# Sheet1.net
KiCad netlist of a schematic drawn in Altium Designer
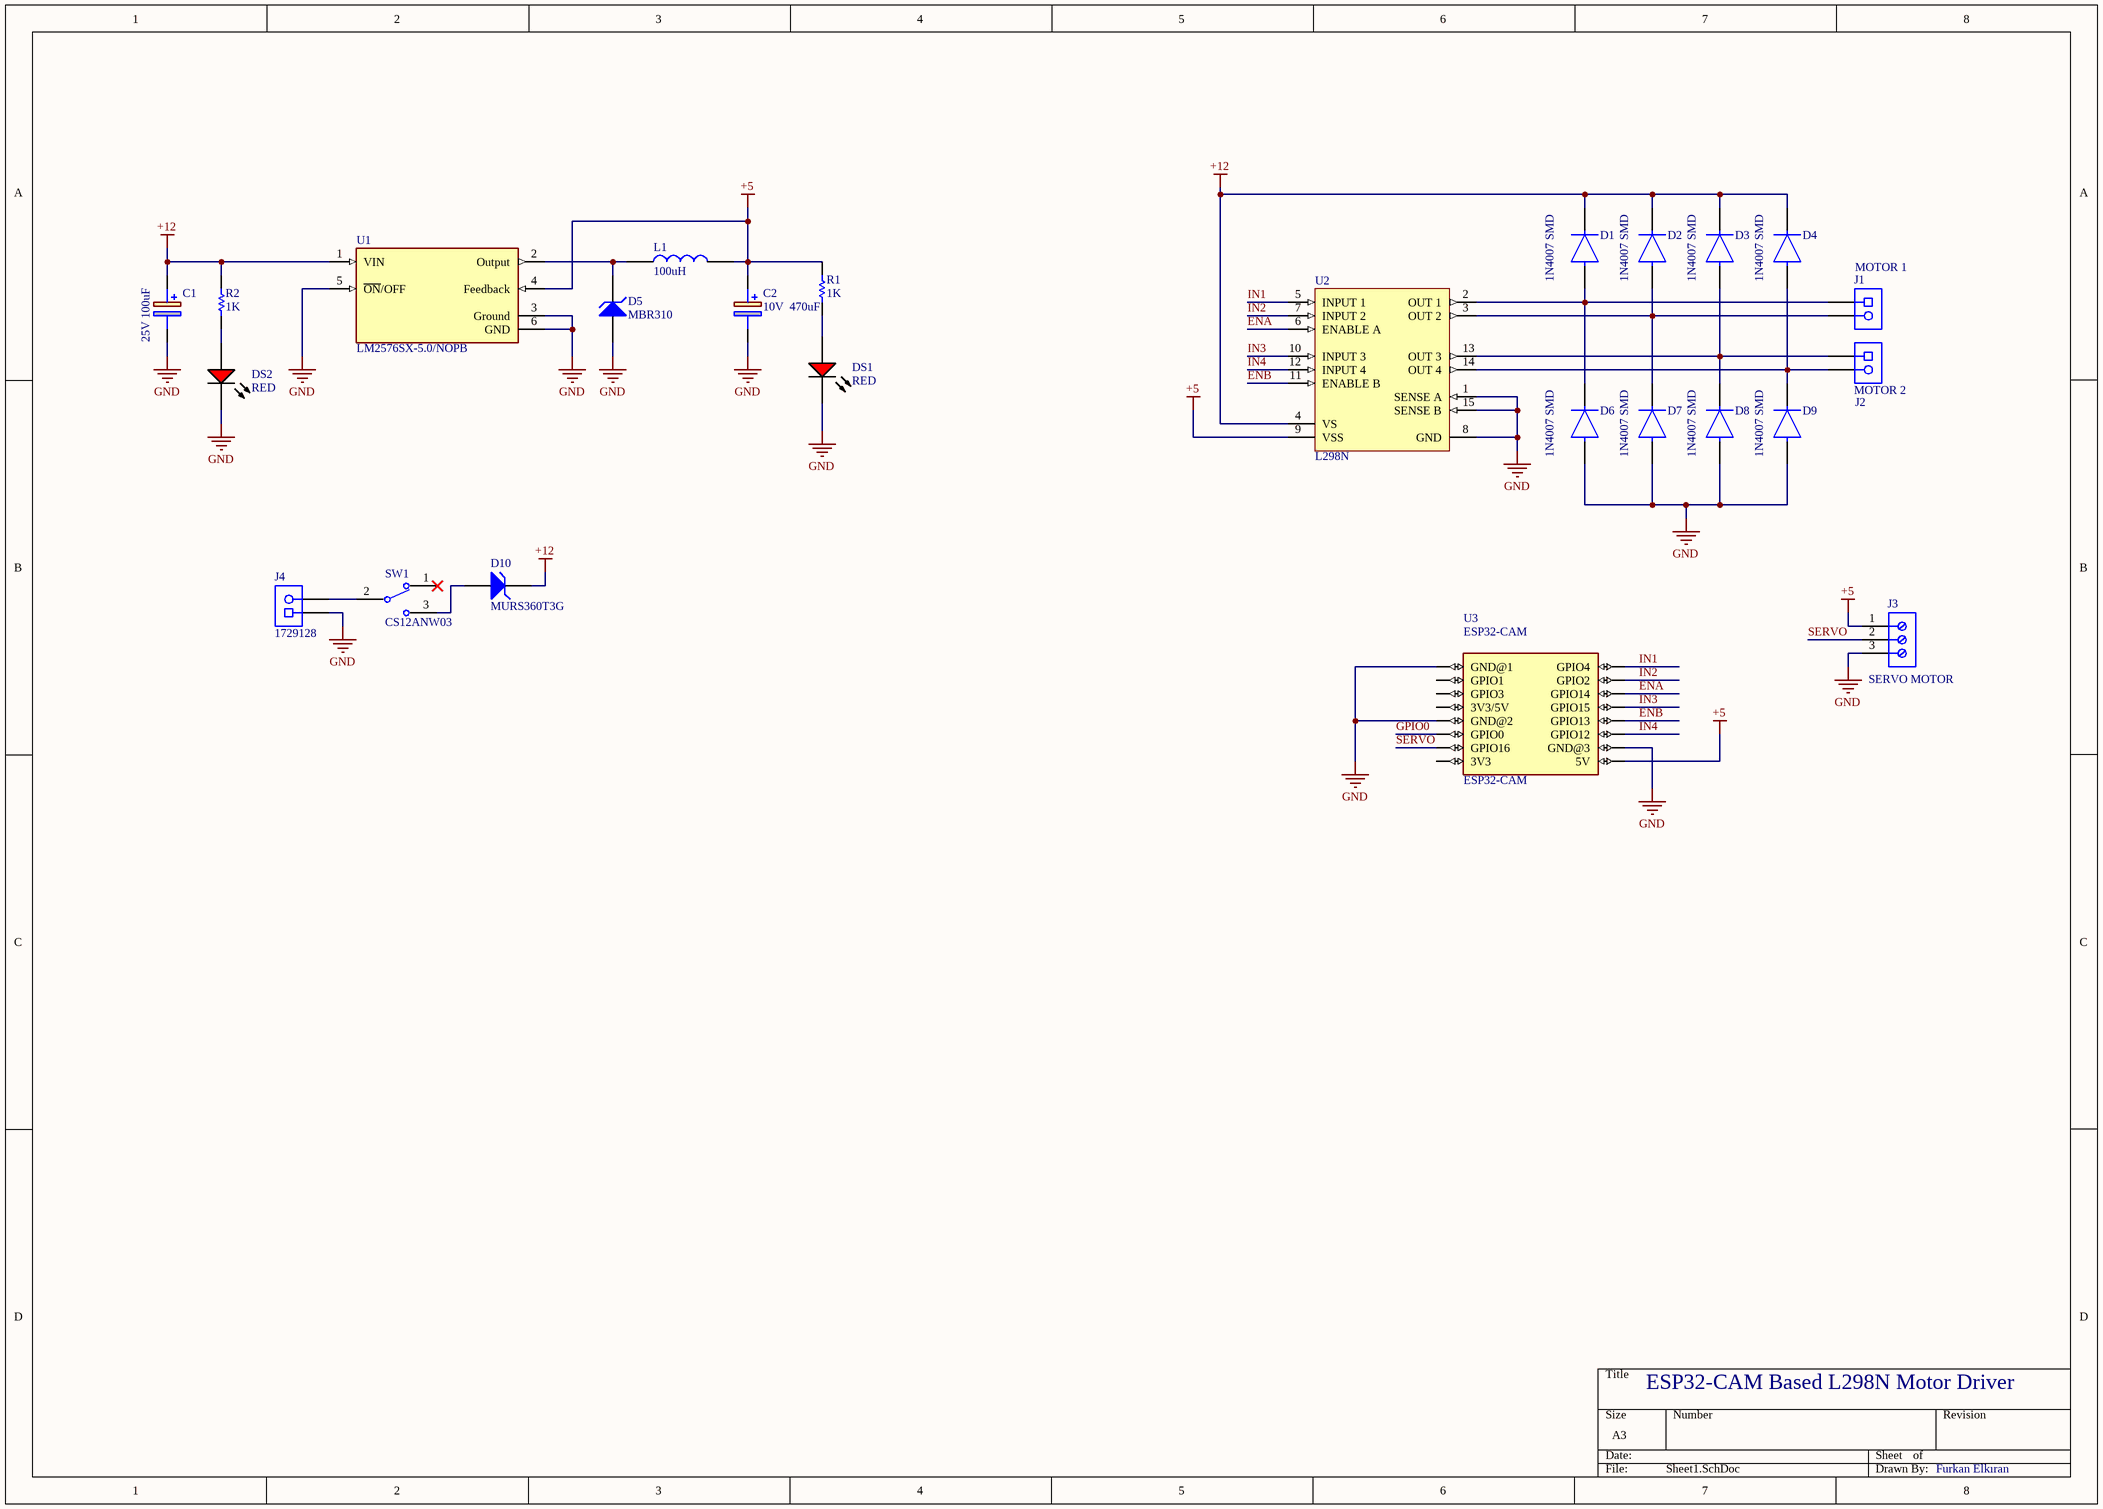
[diagram p0: Sheet1.SchDoc]

(export (version "E")
  (design (tool "Eeschema 10.0.6"))
  (components
    (comp (ref "C1")
      (value "25V 100uF")
      (footprint "EEHZA1E101XP")
      (description "BXJ25VC100MF80TP")
      (fields
        (field (name "MANUFACTURER_PART_NUMBER") "EEH-ZA1E101XP")
        (field (name "MOUSER PART NUMBER") "667-EEH-ZA1E101XP")
      )
      (libsource (lib "EEH-ZA1E101XP") (part "EEH-ZA1E101XP"))
    )
    (comp (ref "C2")
      (value "10V  470uF")
      (footprint "EEHZA1E101XP")
      (description "EEE-FTA471XAP")
      (fields
        (field (name "MANUFACTURER_PART_NUMBER") "EEH-ZA1E101XP")
        (field (name "MOUSER PART NUMBER") "667-EEH-ZA1E101XP")
      )
      (libsource (lib "EEH-ZA1E101XP") (part "EEH-ZA1E101XP"))
    )
    (comp (ref "D1")
      (value "1N4007 SMD")
      (footprint "FP-1N4007_SMD-IPC_C")
      (description "Rectifier, 1Kv, 1A, Do-214Ac Rohs Compliant: Yes")
      (libsource (lib "Altium Content Vault") (part "d7152d700b627762746794eb795d46e"))
    )
    (comp (ref "D2")
      (value "1N4007 SMD")
      (footprint "FP-1N4007_SMD-IPC_C")
      (description "Rectifier, 1Kv, 1A, Do-214Ac Rohs Compliant: Yes")
      (libsource (lib "Altium Content Vault") (part "d7152d700b627762746794eb795d46e"))
    )
    (comp (ref "D3")
      (value "1N4007 SMD")
      (footprint "FP-1N4007_SMD-IPC_C")
      (description "Rectifier, 1Kv, 1A, Do-214Ac Rohs Compliant: Yes")
      (libsource (lib "Altium Content Vault") (part "d7152d700b627762746794eb795d46e"))
    )
    (comp (ref "D4")
      (value "1N4007 SMD")
      (footprint "FP-1N4007_SMD-IPC_C")
      (description "Rectifier, 1Kv, 1A, Do-214Ac Rohs Compliant: Yes")
      (libsource (lib "Altium Content Vault") (part "d7152d700b627762746794eb795d46e"))
    )
    (comp (ref "D5")
      (value "MBR310")
      (footprint "LFUS-DO-214AB-2_V")
      (description "MB310_R1_00001")
      (fields (field (name "MANUFACTURER") "Littelfuse"))
      (libsource (lib "Altium Content Vault") (part "DZEN-AK-2"))
    )
    (comp (ref "D6")
      (value "1N4007 SMD")
      (footprint "FP-1N4007_SMD-IPC_C")
      (description "Rectifier, 1Kv, 1A, Do-214Ac Rohs Compliant: Yes")
      (libsource (lib "Altium Content Vault") (part "d7152d700b627762746794eb795d46e"))
    )
    (comp (ref "D7")
      (value "1N4007 SMD")
      (footprint "FP-1N4007_SMD-IPC_C")
      (description "Rectifier, 1Kv, 1A, Do-214Ac Rohs Compliant: Yes")
      (libsource (lib "Altium Content Vault") (part "d7152d700b627762746794eb795d46e"))
    )
    (comp (ref "D8")
      (value "1N4007 SMD")
      (footprint "FP-1N4007_SMD-IPC_C")
      (description "Rectifier, 1Kv, 1A, Do-214Ac Rohs Compliant: Yes")
      (libsource (lib "Altium Content Vault") (part "d7152d700b627762746794eb795d46e"))
    )
    (comp (ref "D9")
      (value "1N4007 SMD")
      (footprint "FP-1N4007_SMD-IPC_C")
      (description "Rectifier, 1Kv, 1A, Do-214Ac Rohs Compliant: Yes")
      (libsource (lib "Altium Content Vault") (part "d7152d700b627762746794eb795d46e"))
    )
    (comp (ref "D10")
      (value "MURS360T3G")
      (footprint "LFUS-DO-214AB-2_V")
      (fields (field (name "MANUFACTURER") "Littelfuse"))
      (libsource (lib "Altium Content Vault") (part "DZEN-AK-2"))
    )
    (comp (ref "DS1")
      (value "RED")
      (footprint "LUMX-SML-LX1206IC_V")
      (description "HL-PC-3216S9AC")
      (fields (field (name "MANUFACTURER") "Lumex") (field (name "PART NO") "SML-LX1206IC-TR"))
      (libsource (lib "Altium Content Vault") (part "LED-RED-AK-2"))
    )
    (comp (ref "DS2")
      (value "RED")
      (footprint "LUMX-SML-LX1206IC_V")
      (description "HL-PC-3216S9AC")
      (fields (field (name "MANUFACTURER") "Lumex") (field (name "PART NO") "SML-LX1206IC-TR"))
      (libsource (lib "Altium Content Vault") (part "LED-RED-AK-2"))
    )
    (comp (ref "J1")
      (value "MOTOR 1")
      (footprint "PHOE-1729128-2_V")
      (description "PCB Terminal Block, 13.5 A, 400 V, 2-Pin THD, RoHS, Bulk")
      (fields (field (name "PARTNUMBER") "1729128") (field (name "MANUFACTURER") "Phoenix Contact"))
      (libsource (lib "") (part "CN-2P-F-R2_1"))
    )
    (comp (ref "J2")
      (value "MOTOR 2")
      (footprint "PHOE-1729128-2_V")
      (description "PCB Terminal Block, 13.5 A, 400 V, 2-Pin THD, RoHS, Bulk")
      (fields (field (name "PARTNUMBER") "1729128") (field (name "MANUFACTURER") "Phoenix Contact"))
      (libsource (lib "") (part "CN-2P-F-R2_1"))
    )
    (comp (ref "J3")
      (value "SERVO MOTOR")
      (footprint "691214110003")
      (fields (field (name "VOLTAGE") "300V"))
      (libsource (lib "Altium Content Vault") (part "TBL - 1R - 03P - Screw"))
    )
    (comp (ref "J4")
      (value "1729128")
      (footprint "PHOE-1729128-2_V")
      (description "PCB Terminal Block, 13.5 A, 400 V, 2-Pin THD, RoHS, Bulk")
      (fields (field (name "MANUFACTURER") "Phoenix Contact"))
      (libsource (lib "Altium Content Vault") (part "CN-2P-F-R2"))
    )
    (comp (ref "L1")
      (value "100uH")
      (footprint "SRR1260101M")
      (description "SRI1209-101M")
      (fields
        (field (name "MANUFACTURER_PART_NUMBER") "SRR1260-101M")
        (field (name "MOUSER PART NUMBER") "652-SRR1260-101M")
      )
      (libsource (lib "SRR1260-101M") (part "SRR1260-101M"))
    )
    (comp (ref "R1")
      (value "1K")
      (footprint "RESC3216X70X50NL05T20")
      (description "1206S4F1001T5E")
      (fields (field (name "MANUFACTURER") "Panasonic") (field (name "PART NUMBER") "ERJ-8GEY0R00V"))
      (libsource (lib "Altium Content Vault") (part "RES"))
    )
    (comp (ref "R2")
      (value "1K")
      (footprint "RESC3216X70X50NL05T20")
      (description "1206S4F1001T5E")
      (fields (field (name "MANUFACTURER") "Panasonic") (field (name "PART NUMBER") "ERJ-8GEY0R00V"))
      (libsource (lib "Altium Content Vault") (part "RES"))
    )
    (comp (ref "SW1")
      (value "CS12ANW03")
      (footprint "FP-CS12ANW03-MFG")
      (description "SWITCH SLIDE SPDT 3A 125V")
      (libsource (lib "Altium Content Vault") (part "12161840acc88c497b895bf2e19a5b1"))
    )
    (comp (ref "U1")
      (value "LM2576SX-5.0/NOPB")
      (footprint "FP-KTT0005B-MFG")
      (description "IC REG BUCK 5V 3A TO263-5")
      (libsource (lib "Altium Content Vault") (part "f0883da41c58ceda5f27a37e32163a8"))
    )
    (comp (ref "U2")
      (value "L298N")
      (footprint "STM-FM-15")
      (description "Dual Full-Bridge Driver, 4.8 to 46 V, -40 to 150 degC, 15-Pin FM (MW 15L), RoHS, Tube")
      (fields (field (name "MANUFACTURER") "STMicroelectronics") (field (name "PARTNUMBER") "L298"))
      (libsource (lib "Altium Content Vault") (part "STM-L298-15"))
    )
    (comp (ref "U3")
      (value "ESP32-CAM")
      (footprint "ESP32-CAM")
      (libsource (lib "Schlib1") (part "ESP32-CAM"))
    )
  )
  (nets
    (net (code "1") (name "+5") (class "Default")
      (node (ref "C2") (pin "1") (pinfunction "+_1") (pintype "passive"))
      (node (ref "J3") (pin "1") (pinfunction "1_1") (pintype "passive"))
      (node (ref "L1") (pin "2") (pinfunction "2_2") (pintype "passive"))
      (node (ref "R1") (pin "2") (pinfunction "2_2") (pintype "passive"))
      (node (ref "U1") (pin "4") (pinfunction "Feedback_4") (pintype "input"))
      (node (ref "U2") (pin "9") (pinfunction "VSS_9") (pintype "power_in"))
      (node (ref "U3") (pin "P$9") (pinfunction "5V_P$9") (pintype "bidirectional"))
    )
    (net (code "2") (name "+12") (class "Default")
      (node (ref "C1") (pin "1") (pinfunction "+_1") (pintype "passive"))
      (node (ref "D1") (pin "1") (pinfunction "C_1") (pintype "passive"))
      (node (ref "D10") (pin "2") (pinfunction "K_2") (pintype "passive"))
      (node (ref "D2") (pin "1") (pinfunction "C_1") (pintype "passive"))
      (node (ref "D3") (pin "1") (pinfunction "C_1") (pintype "passive"))
      (node (ref "D4") (pin "1") (pinfunction "C_1") (pintype "passive"))
      (node (ref "R2") (pin "2") (pinfunction "2_2") (pintype "passive"))
      (node (ref "U1") (pin "1") (pinfunction "VIN_1") (pintype "input"))
      (node (ref "U2") (pin "4") (pinfunction "VS_4") (pintype "power_in"))
    )
    (net (code "3") (name "/ENA") (class "Default")
      (node (ref "U2") (pin "6") (pinfunction "ENABLE_A_6") (pintype "input"))
      (node (ref "U3") (pin "P$14") (pinfunction "GPIO14_P$14") (pintype "bidirectional"))
    )
    (net (code "4") (name "/ENB") (class "Default")
      (node (ref "U2") (pin "11") (pinfunction "ENABLE_B_11") (pintype "input"))
      (node (ref "U3") (pin "P$12") (pinfunction "GPIO13_P$12") (pintype "bidirectional"))
    )
    (net (code "5") (name "/GPIO0") (class "Default")
      (node (ref "U3") (pin "P$6") (pinfunction "GPIO0_P$6") (pintype "bidirectional"))
    )
    (net (code "6") (name "/IN1") (class "Default")
      (node (ref "U2") (pin "5") (pinfunction "INPUT_1_5") (pintype "input"))
      (node (ref "U3") (pin "P$16") (pinfunction "GPIO4_P$16") (pintype "bidirectional"))
    )
    (net (code "7") (name "/IN2") (class "Default")
      (node (ref "U2") (pin "7") (pinfunction "INPUT_2_7") (pintype "input"))
      (node (ref "U3") (pin "P$15") (pinfunction "GPIO2_P$15") (pintype "bidirectional"))
    )
    (net (code "8") (name "/IN3") (class "Default")
      (node (ref "U2") (pin "10") (pinfunction "INPUT_3_10") (pintype "input"))
      (node (ref "U3") (pin "P$13") (pinfunction "GPIO15_P$13") (pintype "bidirectional"))
    )
    (net (code "9") (name "/IN4") (class "Default")
      (node (ref "U2") (pin "12") (pinfunction "INPUT_4_12") (pintype "input"))
      (node (ref "U3") (pin "P$11") (pinfunction "GPIO12_P$11") (pintype "bidirectional"))
    )
    (net (code "10") (name "/SERVO") (class "Default")
      (node (ref "J3") (pin "2") (pinfunction "2_2") (pintype "passive"))
      (node (ref "U3") (pin "P$7") (pinfunction "GPIO16_P$7") (pintype "bidirectional"))
    )
    (net (code "11") (name "GND") (class "Default")
      (node (ref "C1") (pin "2") (pinfunction "-_2") (pintype "passive"))
      (node (ref "C2") (pin "2") (pinfunction "-_2") (pintype "passive"))
      (node (ref "D5") (pin "1") (pinfunction "A_1") (pintype "passive"))
      (node (ref "D6") (pin "2") (pinfunction "A_2") (pintype "passive"))
      (node (ref "D7") (pin "2") (pinfunction "A_2") (pintype "passive"))
      (node (ref "D8") (pin "2") (pinfunction "A_2") (pintype "passive"))
      (node (ref "D9") (pin "2") (pinfunction "A_2") (pintype "passive"))
      (node (ref "DS1") (pin "2") (pinfunction "K_2") (pintype "passive"))
      (node (ref "DS2") (pin "2") (pinfunction "K_2") (pintype "passive"))
      (node (ref "J3") (pin "3") (pinfunction "3_3") (pintype "passive"))
      (node (ref "J4") (pin "1") (pinfunction "1_1") (pintype "passive"))
      (node (ref "U1") (pin "3") (pinfunction "Ground_3") (pintype "power_in"))
      (node (ref "U1") (pin "5") (pinfunction "~{ON}/OFF_5") (pintype "input"))
      (node (ref "U1") (pin "6") (pinfunction "GND_6") (pintype "power_in"))
      (node (ref "U2") (pin "1") (pinfunction "SENSE_A_1") (pintype "input"))
      (node (ref "U2") (pin "15") (pinfunction "SENSE_B_15") (pintype "input"))
      (node (ref "U2") (pin "8") (pinfunction "GND_8") (pintype "power_in"))
      (node (ref "U3") (pin "P$1") (pinfunction "GND@1_P$1") (pintype "bidirectional"))
      (node (ref "U3") (pin "P$10") (pinfunction "GND@3_P$10") (pintype "bidirectional"))
      (node (ref "U3") (pin "P$5") (pinfunction "GND@2_P$5") (pintype "bidirectional"))
    )
    (net (code "12") (name "Net-(D1-A)") (class "Default")
      (node (ref "D1") (pin "2") (pinfunction "A_2") (pintype "passive"))
      (node (ref "D6") (pin "1") (pinfunction "C_1") (pintype "passive"))
      (node (ref "J1") (pin "1") (pinfunction "1_1") (pintype "passive"))
      (node (ref "U2") (pin "2") (pinfunction "OUT_1_2") (pintype "output"))
    )
    (net (code "13") (name "Net-(D2-A)") (class "Default")
      (node (ref "D2") (pin "2") (pinfunction "A_2") (pintype "passive"))
      (node (ref "D7") (pin "1") (pinfunction "C_1") (pintype "passive"))
      (node (ref "J1") (pin "2") (pinfunction "2_2") (pintype "passive"))
      (node (ref "U2") (pin "3") (pinfunction "OUT_2_3") (pintype "output"))
    )
    (net (code "14") (name "Net-(D3-A)") (class "Default")
      (node (ref "D3") (pin "2") (pinfunction "A_2") (pintype "passive"))
      (node (ref "D8") (pin "1") (pinfunction "C_1") (pintype "passive"))
      (node (ref "J2") (pin "1") (pinfunction "1_1") (pintype "passive"))
      (node (ref "U2") (pin "13") (pinfunction "OUT_3_13") (pintype "output"))
    )
    (net (code "15") (name "Net-(D4-A)") (class "Default")
      (node (ref "D4") (pin "2") (pinfunction "A_2") (pintype "passive"))
      (node (ref "D9") (pin "1") (pinfunction "C_1") (pintype "passive"))
      (node (ref "J2") (pin "2") (pinfunction "2_2") (pintype "passive"))
      (node (ref "U2") (pin "14") (pinfunction "OUT_4_14") (pintype "output"))
    )
    (net (code "16") (name "Net-(D5-K)") (class "Default")
      (node (ref "D5") (pin "2") (pinfunction "K_2") (pintype "passive"))
      (node (ref "L1") (pin "1") (pinfunction "1_1") (pintype "passive"))
      (node (ref "U1") (pin "2") (pinfunction "Output_2") (pintype "output"))
    )
    (net (code "17") (name "Net-(D10-A)") (class "Default")
      (node (ref "D10") (pin "1") (pinfunction "A_1") (pintype "passive"))
      (node (ref "SW1") (pin "3") (pinfunction "3_3") (pintype "passive"))
    )
    (net (code "18") (name "Net-(DS1-A)") (class "Default")
      (node (ref "DS1") (pin "1") (pinfunction "A_1") (pintype "passive"))
      (node (ref "R1") (pin "1") (pinfunction "1_1") (pintype "passive"))
    )
    (net (code "19") (name "Net-(DS2-A)") (class "Default")
      (node (ref "DS2") (pin "1") (pinfunction "A_1") (pintype "passive"))
      (node (ref "R2") (pin "1") (pinfunction "1_1") (pintype "passive"))
    )
    (net (code "20") (name "Net-(SW1-2(COM))") (class "Default")
      (node (ref "J4") (pin "2") (pinfunction "2_2") (pintype "passive"))
      (node (ref "SW1") (pin "2") (pinfunction "2(COM)_2") (pintype "passive"))
    )
    (net (code "21") (name "unconnected-(SW1-Pad1)") (class "Default")
      (node (ref "SW1") (pin "1") (pinfunction "1_1") (pintype "passive+no_connect"))
    )
    (net (code "22") (name "unconnected-(U3-3V3-PadP$8)") (class "Default")
      (node (ref "U3") (pin "P$8") (pinfunction "3V3_P$8") (pintype "bidirectional"))
    )
    (net (code "23") (name "unconnected-(U3-3V3{slash}5V-PadP$4)") (class "Default")
      (node (ref "U3") (pin "P$4") (pinfunction "3V3/5V_P$4") (pintype "bidirectional"))
    )
    (net (code "24") (name "unconnected-(U3-GPIO1-PadP$2)") (class "Default")
      (node (ref "U3") (pin "P$2") (pinfunction "GPIO1_P$2") (pintype "bidirectional"))
    )
    (net (code "25") (name "unconnected-(U3-GPIO3-PadP$3)") (class "Default")
      (node (ref "U3") (pin "P$3") (pinfunction "GPIO3_P$3") (pintype "bidirectional"))
    )
  )
)
